# 4915dec.net
KiCad netlist of a schematic drawn in EAGLE
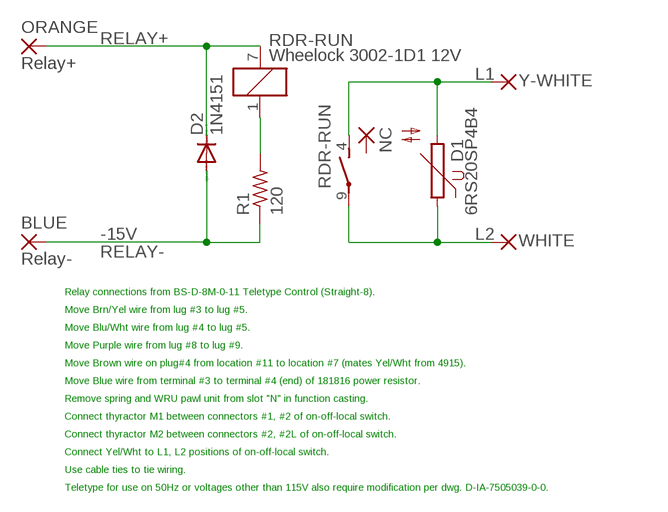
[diagram p0: schematic, sheet 1]

(export (version "E")
  (design (tool "Eeschema 10.0.6"))
  (components
    (comp (ref "BLUE")
      (value "Relay-")
      (footprint "eagle-import:3,17_1,3")
      (libsource (lib "eagle-import") (part "3,17/1,3"))
    )
    (comp (ref "D1")
      (value "6RS20SP4B4")
      (footprint "eagle-import:6RS20SP4B4")
      (libsource (lib "eagle-import") (part "6RS20SP4B4"))
    )
    (comp (ref "D2")
      (value "1N4151")
      (footprint "eagle-import:DO35-10")
      (libsource (lib "eagle-import") (part "1N4148DO35-10"))
    )
    (comp (ref "NC")
      (value "3,17/1,3")
      (footprint "eagle-import:3,17_1,3")
      (libsource (lib "eagle-import") (part "3,17/1,3"))
    )
    (comp (ref "ORANGE")
      (value "Relay+")
      (footprint "eagle-import:3,17_1,3")
      (libsource (lib "eagle-import") (part "3,17/1,3"))
    )
    (comp (ref "R1")
      (value "120")
      (footprint "eagle-import:0207_10")
      (libsource (lib "eagle-import") (part "R-US_0207/10"))
    )
    (comp (ref "RDR-RUN")
      (value "Wheelock 3002-1D1 12V")
      (footprint "eagle-import:3002-1D1")
      (libsource (lib "eagle-import") (part "3002-1D1"))
    )
    (comp (ref "WHITE")
      (value "L2")
      (footprint "eagle-import:3,17_1,3")
      (libsource (lib "eagle-import") (part "3,17/1,3"))
    )
    (comp (ref "Y-WHITE")
      (value "L1")
      (footprint "eagle-import:3,17_1,3")
      (libsource (lib "eagle-import") (part "3,17/1,3"))
    )
  )
  (nets
    (net (code "1") (name "/-15V") (class "Default")
      (node (ref "BLUE") (pin "1") (pinfunction "P_1") (pintype "passive"))
      (node (ref "D2") (pin "A") (pinfunction "A_A") (pintype "passive"))
      (node (ref "R1") (pin "1") (pinfunction "1_1") (pintype "passive"))
    )
    (net (code "2") (name "/L1") (class "Default")
      (node (ref "D1") (pin "2") (pinfunction "2_2") (pintype "passive"))
      (node (ref "RDR-RUN") (pin "4") (pinfunction "4_4") (pintype "passive"))
      (node (ref "Y-WHITE") (pin "1") (pinfunction "P_1") (pintype "passive"))
    )
    (net (code "3") (name "/L2") (class "Default")
      (node (ref "D1") (pin "1") (pinfunction "1_1") (pintype "passive"))
      (node (ref "RDR-RUN") (pin "9") (pinfunction "9_9") (pintype "passive"))
      (node (ref "WHITE") (pin "1") (pinfunction "P_1") (pintype "passive"))
    )
    (net (code "4") (name "/RELAY+") (class "Default")
      (node (ref "D2") (pin "C") (pinfunction "C_C") (pintype "passive"))
      (node (ref "ORANGE") (pin "1") (pinfunction "P_1") (pintype "passive"))
      (node (ref "RDR-RUN") (pin "7") (pinfunction "7_7") (pintype "passive"))
    )
    (net (code "5") (name "Net-(R1-Pad2)") (class "Default")
      (node (ref "R1") (pin "2") (pinfunction "2_2") (pintype "passive"))
      (node (ref "RDR-RUN") (pin "1") (pinfunction "1_1") (pintype "passive"))
    )
    (net (code "6") (name "unconnected-(NC-P-Pad1)") (class "Default")
      (node (ref "NC") (pin "1") (pinfunction "P_1") (pintype "passive"))
    )
  )
)
